# BeagleBoneCape.net
KiCad netlist of a schematic drawn in Altium Designer
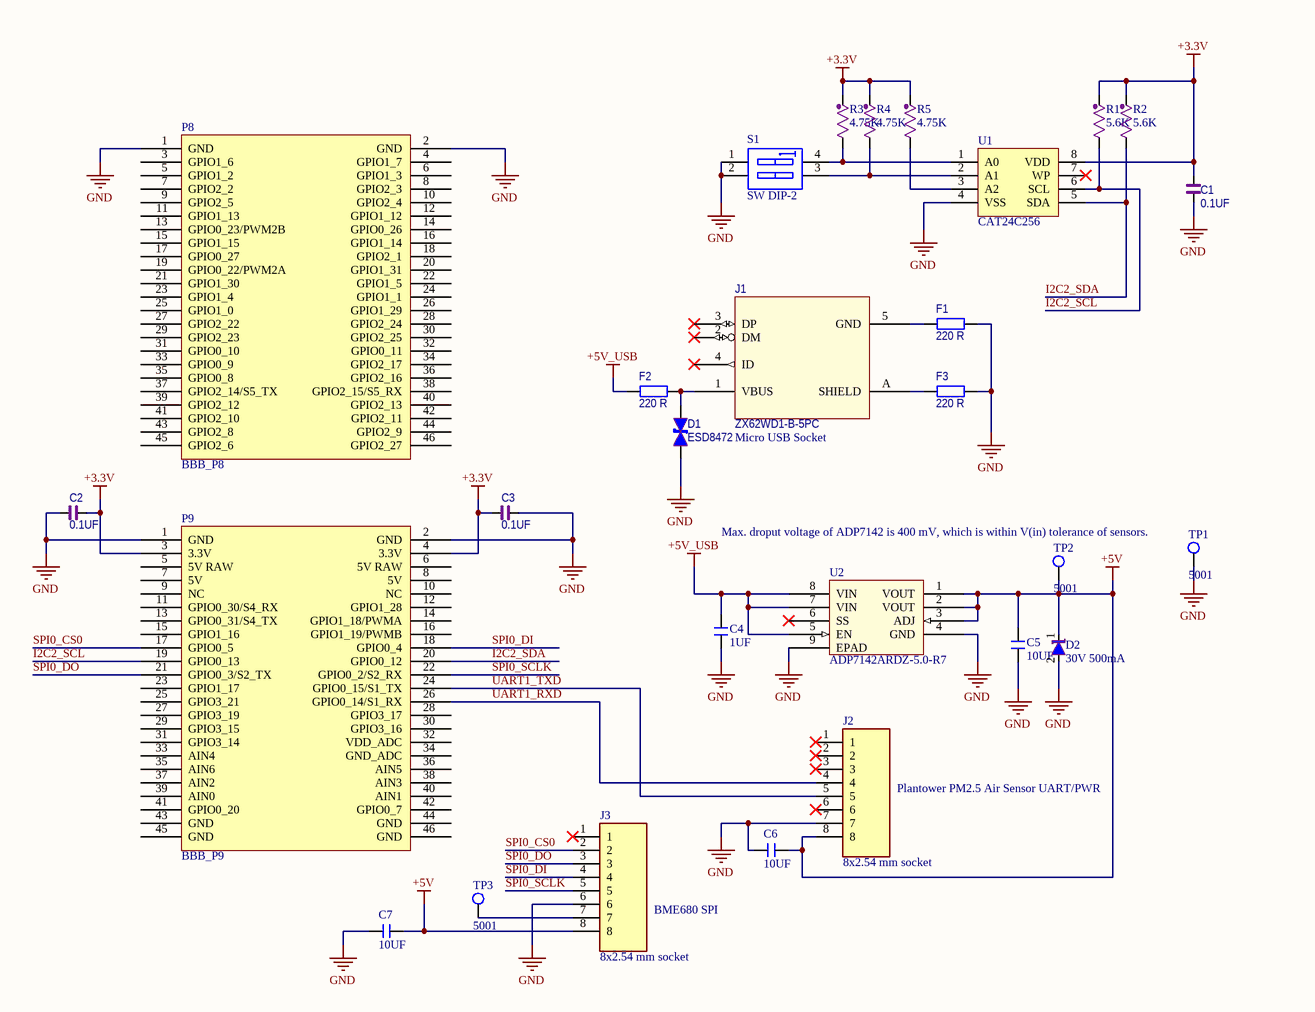
[diagram p0: BeagleBoneCape.SchDoc]

(export (version "E")
  (design (tool "Eeschema 10.0.6"))
  (components
    (comp (ref "C1")
      (value "0.1UF")
      (footprint "0603-CAP")
      (description "0.1µF ±5% 50V Ceramic Capacitor X7R 0603 (1608 Metric)")
      (fields (field (name "VOLTAGE") "50V") (field (name "TOLERANCE") "5%"))
      (libsource (lib "") (part "CAP CER 0.1UF 50V X7R 0603_1"))
    )
    (comp (ref "C2")
      (value "0.1UF")
      (footprint "0603-CAP")
      (description "0.1µF ±5% 50V Ceramic Capacitor X7R 0603 (1608 Metric)")
      (fields (field (name "VOLTAGE") "50V") (field (name "TOLERANCE") "5%"))
      (libsource (lib "BeagleBoneCape_1") (part "CAP CER 0.1UF 50V X7R 0603"))
    )
    (comp (ref "C3")
      (value "0.1UF")
      (footprint "0603-CAP")
      (description "0.1µF ±5% 50V Ceramic Capacitor X7R 0603 (1608 Metric)")
      (fields (field (name "VOLTAGE") "50V") (field (name "TOLERANCE") "5%"))
      (libsource (lib "BeagleBoneCape_1") (part "CAP CER 0.1UF 50V X7R 0603"))
    )
    (comp (ref "C4")
      (value "1UF")
      (footprint "CAPC2013X140N")
      (description "1µF ±10% 25V Ceramic Capacitor X5R 0805 (2012 Metric)")
      (fields (field (name "VOLTAGE") "25V") (field (name "TOLERANCE") "10%"))
      (libsource (lib "BeagleBoneCape_1") (part "CAP_08053D105KAT2A"))
    )
    (comp (ref "C5")
      (value "10UF")
      (footprint "CAPC2013X145N")
      (description "10µF ±10% 25V Ceramic Capacitor X5R 0805 (2012 Metric)")
      (fields (field (name "VOLTAGE") "25V") (field (name "TOLERANCE") "10%"))
      (libsource (lib "BeagleBoneCape_1") (part "CAP_C2012X5R1E106K125AB"))
    )
    (comp (ref "C6")
      (value "10UF")
      (footprint "CAPC2013X145N")
      (description "10µF ±10% 25V Ceramic Capacitor X5R 0805 (2012 Metric)")
      (fields (field (name "VOLTAGE") "25V") (field (name "TOLERANCE") "10%"))
      (libsource (lib "BeagleBoneCape_1") (part "CAP_C2012X5R1E106K125AB"))
    )
    (comp (ref "C7")
      (value "10UF")
      (footprint "CAPC2013X145N")
      (description "10µF ±10% 25V Ceramic Capacitor X5R 0805 (2012 Metric)")
      (fields (field (name "VOLTAGE") "25V") (field (name "TOLERANCE") "10%"))
      (libsource (lib "BeagleBoneCape_1") (part "CAP_C2012X5R1E106K125AB"))
    )
    (comp (ref "D1")
      (value "ESD8472")
      (footprint "0201-TVS")
      (description "20V Clamp 3A (8/20µs) Ipp Tvs Diode Surface Mount 2-X3DFN (0.62x0.32)")
      (fields (field (name "MANF") "ON SEMICONDUCTOR"))
      (libsource (lib "BeagleBoneCape_1") (part "ESD8472"))
    )
    (comp (ref "D2")
      (value "30V 500mA")
      (footprint "SOD-323")
      (description "Diode Schottky 30V 500mA (DC) Surface Mount SOD-323")
      (fields (field (name "MANF") "ON Semi"))
      (libsource (lib "BeagleBoneCape_1") (part "DIODE SCHOTTKY 30V 500MA SOD323"))
    )
    (comp (ref "F1")
      (value "220 R")
      (footprint "INDC1005X55N")
      (description "220 Ohms @ 100MHz 1  Ferrite Bead 0402 (1005 Metric) 700mA 280mOhm")
      (fields (field (name "MANF") "Murata"))
      (libsource (lib "BeagleBoneCape_1") (part "FB_BLM15EG221SN1D"))
    )
    (comp (ref "F2")
      (value "220 R")
      (footprint "INDC1005X55N")
      (description "220 Ohms @ 100MHz 1  Ferrite Bead 0402 (1005 Metric) 700mA 280mOhm")
      (fields (field (name "MANF") "Murata"))
      (libsource (lib "BeagleBoneCape_1") (part "FB_BLM15EG221SN1D"))
    )
    (comp (ref "F3")
      (value "220 R")
      (footprint "INDC1005X55N")
      (description "220 Ohms @ 100MHz 1  Ferrite Bead 0402 (1005 Metric) 700mA 280mOhm")
      (fields (field (name "MANF") "Murata"))
      (libsource (lib "BeagleBoneCape_1") (part "FB_BLM15EG221SN1D"))
    )
    (comp (ref "J1")
      (value "ZX62WD1-B-5PC")
      (footprint "HIROSE_ZX62WD1-B-5PC")
      (description "USB - micro B USB 2.0 Receptacle Connector 5 Position Surface Mount, Right Angle")
      (fields (field (name "MANF") "Hirose Electric Co Ltd") (field (name "NOTE") "Micro USB Socket"))
      (libsource (lib "BeagleBoneCape_1") (part "USB2_MICRO"))
    )
    (comp (ref "J2")
      (value "8x2.54 mm socket")
      (footprint "HDR1X8")
      (description "0.1\" 8 pin thru hole receptacle")
      (fields (field (name "MFG") "Sullins Connector Solutions"))
      (libsource (lib "BeagleBoneCape_1") (part "HDR_TH_2.54_8"))
    )
    (comp (ref "J3")
      (value "8x2.54 mm socket")
      (footprint "HDR1X8")
      (description "0.1\" 8 pin thru hole receptacle")
      (fields (field (name "MFG") "Sullins Connector Solutions"))
      (libsource (lib "BeagleBoneCape_1") (part "HDR_TH_2.54_8"))
    )
    (comp (ref "P8")
      (value "BBB_P8")
      (footprint "BBB_CAPE_HEADER")
      (libsource (lib "BeagleBoneCape_1") (part "BBB_P8"))
    )
    (comp (ref "P9")
      (value "BBB_P9")
      (footprint "BBB_CAPE_HEADER")
      (libsource (lib "BeagleBoneCape_1") (part "BBB_P9"))
    )
    (comp (ref "R1")
      (value "5.6K")
      (footprint "0603-RES")
      (description "RES SMD 5.6K 0.1% 1/10W 0603")
      (fields (field (name "MFG") "Yageo"))
      (libsource (lib "BeagleBoneCape_1") (part "RES_5.6K_0.1%_1/10_0603"))
    )
    (comp (ref "R2")
      (value "5.6K")
      (footprint "0603-RES")
      (description "RES SMD 5.6K 0.1% 1/10W 0603")
      (fields (field (name "MFG") "Yageo"))
      (libsource (lib "BeagleBoneCape_1") (part "RES_5.6K_0.1%_1/10_0603"))
    )
    (comp (ref "R3")
      (value "4.75K")
      (footprint "0603-RES")
      (description "RES SMD 4.75K 0.1% 1/10W 0603")
      (fields (field (name "MFG") "Yageo"))
      (libsource (lib "BeagleBoneCape") (part "RES_4.75K_0.1%_1/10_0603"))
    )
    (comp (ref "R4")
      (value "4.75K")
      (footprint "0603-RES")
      (description "RES SMD 4.75K 0.1% 1/10W 0603")
      (fields (field (name "MFG") "Yageo"))
      (libsource (lib "BeagleBoneCape") (part "RES_4.75K_0.1%_1/10_0603"))
    )
    (comp (ref "R5")
      (value "4.75K")
      (footprint "0603-RES")
      (description "RES SMD 4.75K 0.1% 1/10W 0603")
      (fields (field (name "MFG") "Yageo"))
      (libsource (lib "BeagleBoneCape") (part "RES_4.75K_0.1%_1/10_0603"))
    )
    (comp (ref "S1")
      (value "SW DIP-2")
      (footprint "DIP-4")
      (description "DIP Switch, 2 Position, SPST")
      (fields (field (name "PUBLISHER") "Altium Limited"))
      (libsource (lib "BeagleBoneCape_1") (part "SW DIP-2"))
    )
    (comp (ref "TP1")
      (value "5001")
      (footprint "KEYSTONE_5001")
      (description "Test Point, Black, 1-Pin THD, RoHS, Bulk")
      (fields (field (name "MANF") "Keystone"))
      (libsource (lib "BeagleBoneCape_1") (part "TP_5001"))
    )
    (comp (ref "TP2")
      (value "5001")
      (footprint "KEYSTONE_5001")
      (description "Test Point, Black, 1-Pin THD, RoHS, Bulk")
      (fields (field (name "MANF") "Keystone"))
      (libsource (lib "BeagleBoneCape_1") (part "TP_5001"))
    )
    (comp (ref "TP3")
      (value "5001")
      (footprint "KEYSTONE_5001")
      (description "Test Point, Black, 1-Pin THD, RoHS, Bulk")
      (fields (field (name "MANF") "Keystone"))
      (libsource (lib "BeagleBoneCape_1") (part "TP_5001"))
    )
    (comp (ref "U1")
      (value "CAT24C256")
      (footprint "SOIC127P600X175-8N")
      (description "EEPROM Memory IC 256Kb _32K x 8_ I2C 1MHz 500ns 8-SOIC")
      (fields (field (name "MFG") "OnSemi"))
      (libsource (lib "BeagleBoneCape_1") (part "CAT24C256"))
    )
    (comp (ref "U2")
      (value "ADP7142ARDZ-5.0-R7")
      (footprint "SOIC127P600X175-9N_ALT")
      (description "Linear Voltage Regulator IC  1 Output  200mA 8-SOIC-EP")
      (fields (field (name "MANF") "Analog Devices"))
      (libsource (lib "BeagleBoneCape_1") (part "IC_ADP7142ARDZ-5.0-R7"))
    )
  )
  (nets
    (net (code "1") (name "+3.3V") (class "Default")
      (node (ref "C1") (pin "1") (pinfunction "1_1") (pintype "passive"))
      (node (ref "C2") (pin "2") (pinfunction "2_2") (pintype "passive"))
      (node (ref "C3") (pin "1") (pinfunction "1_1") (pintype "passive"))
      (node (ref "P9") (pin "3") (pinfunction "3.3V_3") (pintype "passive"))
      (node (ref "P9") (pin "4") (pinfunction "3.3V_4") (pintype "passive"))
      (node (ref "R1") (pin "2") (pinfunction "2_2") (pintype "passive"))
      (node (ref "R2") (pin "2") (pinfunction "2_2") (pintype "passive"))
      (node (ref "R3") (pin "2") (pinfunction "2_2") (pintype "passive"))
      (node (ref "R4") (pin "2") (pinfunction "2_2") (pintype "passive"))
      (node (ref "R5") (pin "2") (pinfunction "2_2") (pintype "passive"))
      (node (ref "U1") (pin "8") (pinfunction "VDD_8") (pintype "passive"))
    )
    (net (code "2") (name "+5V") (class "Default")
      (node (ref "C5") (pin "1") (pinfunction "1_1") (pintype "passive"))
      (node (ref "C6") (pin "2") (pinfunction "2_2") (pintype "passive"))
      (node (ref "C7") (pin "1") (pinfunction "1_1") (pintype "passive"))
      (node (ref "D2") (pin "1") (pinfunction "1_1") (pintype "passive"))
      (node (ref "J2") (pin "8") (pinfunction "8_8") (pintype "passive"))
      (node (ref "J3") (pin "8") (pinfunction "8_8") (pintype "passive"))
      (node (ref "TP2") (pin "1") (pinfunction "1_1") (pintype "passive"))
      (node (ref "U2") (pin "1") (pinfunction "VOUT_1") (pintype "power_in"))
      (node (ref "U2") (pin "2") (pinfunction "VOUT_2") (pintype "power_in"))
      (node (ref "U2") (pin "3") (pinfunction "ADJ_3") (pintype "input"))
    )
    (net (code "3") (name "+5V_USB") (class "Default")
      (node (ref "C4") (pin "1") (pinfunction "1_1") (pintype "passive"))
      (node (ref "F2") (pin "1") (pinfunction "1_1") (pintype "passive"))
      (node (ref "U2") (pin "5") (pinfunction "EN_5") (pintype "input"))
      (node (ref "U2") (pin "7") (pinfunction "VIN_7") (pintype "power_in"))
      (node (ref "U2") (pin "8") (pinfunction "VIN_8") (pintype "power_in"))
    )
    (net (code "4") (name "/I2C2_SCL") (class "Default")
      (node (ref "P9") (pin "19") (pinfunction "GPIO0_13_19") (pintype "passive"))
      (node (ref "R1") (pin "1") (pinfunction "1_1") (pintype "passive"))
      (node (ref "U1") (pin "6") (pinfunction "SCL_6") (pintype "passive"))
    )
    (net (code "5") (name "/I2C2_SDA") (class "Default")
      (node (ref "P9") (pin "20") (pinfunction "GPIO0_12_20") (pintype "passive"))
      (node (ref "R2") (pin "1") (pinfunction "1_1") (pintype "passive"))
      (node (ref "U1") (pin "5") (pinfunction "SDA_5") (pintype "passive"))
    )
    (net (code "6") (name "/SPI0_CS0") (class "Default")
      (node (ref "J3") (pin "2") (pinfunction "2_2") (pintype "passive"))
      (node (ref "P9") (pin "17") (pinfunction "GPIO0_5_17") (pintype "passive"))
    )
    (net (code "7") (name "/SPI0_DI") (class "Default")
      (node (ref "J3") (pin "4") (pinfunction "4_4") (pintype "passive"))
      (node (ref "P9") (pin "18") (pinfunction "GPIO0_4_18") (pintype "passive"))
    )
    (net (code "8") (name "/SPI0_DO") (class "Default")
      (node (ref "J3") (pin "3") (pinfunction "3_3") (pintype "passive"))
      (node (ref "P9") (pin "21") (pinfunction "GPIO0_3/S2_TX_21") (pintype "passive"))
    )
    (net (code "9") (name "/SPI0_SCLK") (class "Default")
      (node (ref "J3") (pin "5") (pinfunction "5_5") (pintype "passive"))
      (node (ref "P9") (pin "22") (pinfunction "GPIO0_2/S2_RX_22") (pintype "passive"))
    )
    (net (code "10") (name "/UART1_RXD") (class "Default")
      (node (ref "J2") (pin "4") (pinfunction "4_4") (pintype "passive"))
      (node (ref "P9") (pin "26") (pinfunction "GPIO0_14/S1_RX_26") (pintype "passive"))
    )
    (net (code "11") (name "/UART1_TXD") (class "Default")
      (node (ref "J2") (pin "5") (pinfunction "5_5") (pintype "passive"))
      (node (ref "P9") (pin "24") (pinfunction "GPIO0_15/S1_TX_24") (pintype "passive"))
    )
    (net (code "12") (name "GND") (class "Default")
      (node (ref "C1") (pin "2") (pinfunction "2_2") (pintype "passive"))
      (node (ref "C2") (pin "1") (pinfunction "1_1") (pintype "passive"))
      (node (ref "C3") (pin "2") (pinfunction "2_2") (pintype "passive"))
      (node (ref "C4") (pin "2") (pinfunction "2_2") (pintype "passive"))
      (node (ref "C5") (pin "2") (pinfunction "2_2") (pintype "passive"))
      (node (ref "C6") (pin "1") (pinfunction "1_1") (pintype "passive"))
      (node (ref "C7") (pin "2") (pinfunction "2_2") (pintype "passive"))
      (node (ref "D1") (pin "1") (pinfunction "1_1") (pintype "passive"))
      (node (ref "D2") (pin "2") (pinfunction "2_2") (pintype "passive"))
      (node (ref "F1") (pin "2") (pinfunction "2_2") (pintype "passive"))
      (node (ref "F3") (pin "2") (pinfunction "2_2") (pintype "passive"))
      (node (ref "J2") (pin "7") (pinfunction "7_7") (pintype "passive"))
      (node (ref "J3") (pin "6") (pinfunction "6_6") (pintype "passive"))
      (node (ref "P8") (pin "1") (pinfunction "GND_1") (pintype "passive"))
      (node (ref "P8") (pin "2") (pinfunction "GND_2") (pintype "passive"))
      (node (ref "P9") (pin "1") (pinfunction "GND_1") (pintype "passive"))
      (node (ref "P9") (pin "2") (pinfunction "GND_2") (pintype "passive"))
      (node (ref "S1") (pin "1") (pinfunction "A1_1") (pintype "passive"))
      (node (ref "S1") (pin "2") (pinfunction "A2_2") (pintype "passive"))
      (node (ref "TP1") (pin "1") (pinfunction "1_1") (pintype "passive"))
      (node (ref "U1") (pin "4") (pinfunction "VSS_4") (pintype "passive"))
      (node (ref "U2") (pin "4") (pinfunction "GND_4") (pintype "passive"))
      (node (ref "U2") (pin "9") (pinfunction "EPAD_9") (pintype "passive"))
    )
    (net (code "13") (name "Net-(J1-GND)") (class "Default")
      (node (ref "F1") (pin "1") (pinfunction "1_1") (pintype "passive"))
      (node (ref "J1") (pin "5") (pinfunction "GND_5") (pintype "passive"))
    )
    (net (code "14") (name "Net-(J1-SHIELD)") (class "Default")
      (node (ref "F3") (pin "1") (pinfunction "1_1") (pintype "passive"))
      (node (ref "J1") (pin "A") (pinfunction "SHIELD_A") (pintype "passive"))
    )
    (net (code "15") (name "Net-(J1-VBUS)") (class "Default")
      (node (ref "D1") (pin "2") (pinfunction "2_2") (pintype "passive"))
      (node (ref "F2") (pin "2") (pinfunction "2_2") (pintype "passive"))
      (node (ref "J1") (pin "1") (pinfunction "VBUS_1") (pintype "passive"))
    )
    (net (code "16") (name "Net-(J3-Pad7)") (class "Default")
      (node (ref "J3") (pin "7") (pinfunction "7_7") (pintype "passive"))
      (node (ref "TP3") (pin "1") (pinfunction "1_1") (pintype "passive"))
    )
    (net (code "17") (name "Net-(S1-B1)") (class "Default")
      (node (ref "R3") (pin "1") (pinfunction "1_1") (pintype "passive"))
      (node (ref "S1") (pin "4") (pinfunction "B1_4") (pintype "passive"))
      (node (ref "U1") (pin "1") (pinfunction "A0_1") (pintype "passive"))
    )
    (net (code "18") (name "Net-(S1-B2)") (class "Default")
      (node (ref "R4") (pin "1") (pinfunction "1_1") (pintype "passive"))
      (node (ref "S1") (pin "3") (pinfunction "B2_3") (pintype "passive"))
      (node (ref "U1") (pin "2") (pinfunction "A1_2") (pintype "passive"))
    )
    (net (code "19") (name "Net-(U1-A2)") (class "Default")
      (node (ref "R5") (pin "1") (pinfunction "1_1") (pintype "passive"))
      (node (ref "U1") (pin "3") (pinfunction "A2_3") (pintype "passive"))
    )
    (net (code "20") (name "unconnected-(J1-DM-Pad2)") (class "Default")
      (node (ref "J1") (pin "2") (pinfunction "DM_2") (pintype "bidirectional+no_connect"))
    )
    (net (code "21") (name "unconnected-(J1-DP-Pad3)") (class "Default")
      (node (ref "J1") (pin "3") (pinfunction "DP_3") (pintype "bidirectional+no_connect"))
    )
    (net (code "22") (name "unconnected-(J1-ID-Pad4)") (class "Default")
      (node (ref "J1") (pin "4") (pinfunction "ID_4") (pintype "output+no_connect"))
    )
    (net (code "23") (name "unconnected-(J2-Pad1)") (class "Default")
      (node (ref "J2") (pin "1") (pinfunction "1_1") (pintype "passive+no_connect"))
    )
    (net (code "24") (name "unconnected-(J2-Pad2)") (class "Default")
      (node (ref "J2") (pin "2") (pinfunction "2_2") (pintype "passive+no_connect"))
    )
    (net (code "25") (name "unconnected-(J2-Pad3)") (class "Default")
      (node (ref "J2") (pin "3") (pinfunction "3_3") (pintype "passive+no_connect"))
    )
    (net (code "26") (name "unconnected-(J2-Pad6)") (class "Default")
      (node (ref "J2") (pin "6") (pinfunction "6_6") (pintype "passive+no_connect"))
    )
    (net (code "27") (name "unconnected-(J3-Pad1)") (class "Default")
      (node (ref "J3") (pin "1") (pinfunction "1_1") (pintype "passive+no_connect"))
    )
    (net (code "28") (name "unconnected-(P8-GPIO0_8-Pad35)") (class "Default")
      (node (ref "P8") (pin "35") (pinfunction "GPIO0_8_35") (pintype "passive"))
    )
    (net (code "29") (name "unconnected-(P8-GPIO0_9-Pad33)") (class "Default")
      (node (ref "P8") (pin "33") (pinfunction "GPIO0_9_33") (pintype "passive"))
    )
    (net (code "30") (name "unconnected-(P8-GPIO0_10-Pad31)") (class "Default")
      (node (ref "P8") (pin "31") (pinfunction "GPIO0_10_31") (pintype "passive"))
    )
    (net (code "31") (name "unconnected-(P8-GPIO0_11-Pad32)") (class "Default")
      (node (ref "P8") (pin "32") (pinfunction "GPIO0_11_32") (pintype "passive"))
    )
    (net (code "32") (name "unconnected-(P8-GPIO0_22{slash}PWM2A-Pad19)") (class "Default")
      (node (ref "P8") (pin "19") (pinfunction "GPIO0_22/PWM2A_19") (pintype "passive"))
    )
    (net (code "33") (name "unconnected-(P8-GPIO0_23{slash}PWM2B-Pad13)") (class "Default")
      (node (ref "P8") (pin "13") (pinfunction "GPIO0_23/PWM2B_13") (pintype "passive"))
    )
    (net (code "34") (name "unconnected-(P8-GPIO0_26-Pad14)") (class "Default")
      (node (ref "P8") (pin "14") (pinfunction "GPIO0_26_14") (pintype "passive"))
    )
    (net (code "35") (name "unconnected-(P8-GPIO0_27-Pad17)") (class "Default")
      (node (ref "P8") (pin "17") (pinfunction "GPIO0_27_17") (pintype "passive"))
    )
    (net (code "36") (name "unconnected-(P8-GPIO1_0-Pad25)") (class "Default")
      (node (ref "P8") (pin "25") (pinfunction "GPIO1_0_25") (pintype "passive"))
    )
    (net (code "37") (name "unconnected-(P8-GPIO1_1-Pad24)") (class "Default")
      (node (ref "P8") (pin "24") (pinfunction "GPIO1_1_24") (pintype "passive"))
    )
    (net (code "38") (name "unconnected-(P8-GPIO1_2-Pad5)") (class "Default")
      (node (ref "P8") (pin "5") (pinfunction "GPIO1_2_5") (pintype "passive"))
    )
    (net (code "39") (name "unconnected-(P8-GPIO1_3-Pad6)") (class "Default")
      (node (ref "P8") (pin "6") (pinfunction "GPIO1_3_6") (pintype "passive"))
    )
    (net (code "40") (name "unconnected-(P8-GPIO1_4-Pad23)") (class "Default")
      (node (ref "P8") (pin "23") (pinfunction "GPIO1_4_23") (pintype "passive"))
    )
    (net (code "41") (name "unconnected-(P8-GPIO1_5-Pad22)") (class "Default")
      (node (ref "P8") (pin "22") (pinfunction "GPIO1_5_22") (pintype "passive"))
    )
    (net (code "42") (name "unconnected-(P8-GPIO1_6-Pad3)") (class "Default")
      (node (ref "P8") (pin "3") (pinfunction "GPIO1_6_3") (pintype "passive"))
    )
    (net (code "43") (name "unconnected-(P8-GPIO1_7-Pad4)") (class "Default")
      (node (ref "P8") (pin "4") (pinfunction "GPIO1_7_4") (pintype "passive"))
    )
    (net (code "44") (name "unconnected-(P8-GPIO1_12-Pad12)") (class "Default")
      (node (ref "P8") (pin "12") (pinfunction "GPIO1_12_12") (pintype "passive"))
    )
    (net (code "45") (name "unconnected-(P8-GPIO1_13-Pad11)") (class "Default")
      (node (ref "P8") (pin "11") (pinfunction "GPIO1_13_11") (pintype "passive"))
    )
    (net (code "46") (name "unconnected-(P8-GPIO1_14-Pad16)") (class "Default")
      (node (ref "P8") (pin "16") (pinfunction "GPIO1_14_16") (pintype "passive"))
    )
    (net (code "47") (name "unconnected-(P8-GPIO1_15-Pad15)") (class "Default")
      (node (ref "P8") (pin "15") (pinfunction "GPIO1_15_15") (pintype "passive"))
    )
    (net (code "48") (name "unconnected-(P8-GPIO1_29-Pad26)") (class "Default")
      (node (ref "P8") (pin "26") (pinfunction "GPIO1_29_26") (pintype "passive"))
    )
    (net (code "49") (name "unconnected-(P8-GPIO1_30-Pad21)") (class "Default")
      (node (ref "P8") (pin "21") (pinfunction "GPIO1_30_21") (pintype "passive"))
    )
    (net (code "50") (name "unconnected-(P8-GPIO1_31-Pad20)") (class "Default")
      (node (ref "P8") (pin "20") (pinfunction "GPIO1_31_20") (pintype "passive"))
    )
    (net (code "51") (name "unconnected-(P8-GPIO2_1-Pad18)") (class "Default")
      (node (ref "P8") (pin "18") (pinfunction "GPIO2_1_18") (pintype "passive"))
    )
    (net (code "52") (name "unconnected-(P8-GPIO2_2-Pad7)") (class "Default")
      (node (ref "P8") (pin "7") (pinfunction "GPIO2_2_7") (pintype "passive"))
    )
    (net (code "53") (name "unconnected-(P8-GPIO2_3-Pad8)") (class "Default")
      (node (ref "P8") (pin "8") (pinfunction "GPIO2_3_8") (pintype "passive"))
    )
    (net (code "54") (name "unconnected-(P8-GPIO2_4-Pad10)") (class "Default")
      (node (ref "P8") (pin "10") (pinfunction "GPIO2_4_10") (pintype "passive"))
    )
    (net (code "55") (name "unconnected-(P8-GPIO2_5-Pad9)") (class "Default")
      (node (ref "P8") (pin "9") (pinfunction "GPIO2_5_9") (pintype "passive"))
    )
    (net (code "56") (name "unconnected-(P8-GPIO2_6-Pad45)") (class "Default")
      (node (ref "P8") (pin "45") (pinfunction "GPIO2_6_45") (pintype "passive"))
    )
    (net (code "57") (name "unconnected-(P8-GPIO2_8-Pad43)") (class "Default")
      (node (ref "P8") (pin "43") (pinfunction "GPIO2_8_43") (pintype "passive"))
    )
    (net (code "58") (name "unconnected-(P8-GPIO2_9-Pad44)") (class "Default")
      (node (ref "P8") (pin "44") (pinfunction "GPIO2_9_44") (pintype "passive"))
    )
    (net (code "59") (name "unconnected-(P8-GPIO2_10-Pad41)") (class "Default")
      (node (ref "P8") (pin "41") (pinfunction "GPIO2_10_41") (pintype "passive"))
    )
    (net (code "60") (name "unconnected-(P8-GPIO2_11-Pad42)") (class "Default")
      (node (ref "P8") (pin "42") (pinfunction "GPIO2_11_42") (pintype "passive"))
    )
    (net (code "61") (name "unconnected-(P8-GPIO2_12-Pad39)") (class "Default")
      (node (ref "P8") (pin "39") (pinfunction "GPIO2_12_39") (pintype "passive"))
    )
    (net (code "62") (name "unconnected-(P8-GPIO2_13-Pad40)") (class "Default")
      (node (ref "P8") (pin "40") (pinfunction "GPIO2_13_40") (pintype "passive"))
    )
    (net (code "63") (name "unconnected-(P8-GPIO2_14{slash}S5_TX-Pad37)") (class "Default")
      (node (ref "P8") (pin "37") (pinfunction "GPIO2_14/S5_TX_37") (pintype "passive"))
    )
    (net (code "64") (name "unconnected-(P8-GPIO2_15{slash}S5_RX-Pad38)") (class "Default")
      (node (ref "P8") (pin "38") (pinfunction "GPIO2_15/S5_RX_38") (pintype "passive"))
    )
    (net (code "65") (name "unconnected-(P8-GPIO2_16-Pad36)") (class "Default")
      (node (ref "P8") (pin "36") (pinfunction "GPIO2_16_36") (pintype "passive"))
    )
    (net (code "66") (name "unconnected-(P8-GPIO2_17-Pad34)") (class "Default")
      (node (ref "P8") (pin "34") (pinfunction "GPIO2_17_34") (pintype "passive"))
    )
    (net (code "67") (name "unconnected-(P8-GPIO2_22-Pad27)") (class "Default")
      (node (ref "P8") (pin "27") (pinfunction "GPIO2_22_27") (pintype "passive"))
    )
    (net (code "68") (name "unconnected-(P8-GPIO2_23-Pad29)") (class "Default")
      (node (ref "P8") (pin "29") (pinfunction "GPIO2_23_29") (pintype "passive"))
    )
    (net (code "69") (name "unconnected-(P8-GPIO2_24-Pad28)") (class "Default")
      (node (ref "P8") (pin "28") (pinfunction "GPIO2_24_28") (pintype "passive"))
    )
    (net (code "70") (name "unconnected-(P8-GPIO2_25-Pad30)") (class "Default")
      (node (ref "P8") (pin "30") (pinfunction "GPIO2_25_30") (pintype "passive"))
    )
    (net (code "71") (name "unconnected-(P8-GPIO2_27-Pad46)") (class "Default")
      (node (ref "P8") (pin "46") (pinfunction "GPIO2_27_46") (pintype "passive"))
    )
    (net (code "72") (name "unconnected-(P9-5V-Pad7)") (class "Default")
      (node (ref "P9") (pin "7") (pinfunction "5V_7") (pintype "passive"))
    )
    (net (code "73") (name "unconnected-(P9-5V-Pad8)") (class "Default")
      (node (ref "P9") (pin "8") (pinfunction "5V_8") (pintype "passive"))
    )
    (net (code "74") (name "unconnected-(P9-5V_RAW-Pad5)") (class "Default")
      (node (ref "P9") (pin "5") (pinfunction "5V_RAW_5") (pintype "passive"))
    )
    (net (code "75") (name "unconnected-(P9-5V_RAW-Pad6)") (class "Default")
      (node (ref "P9") (pin "6") (pinfunction "5V_RAW_6") (pintype "passive"))
    )
    (net (code "76") (name "unconnected-(P9-AIN0-Pad39)") (class "Default")
      (node (ref "P9") (pin "39") (pinfunction "AIN0_39") (pintype "passive"))
    )
    (net (code "77") (name "unconnected-(P9-AIN1-Pad40)") (class "Default")
      (node (ref "P9") (pin "40") (pinfunction "AIN1_40") (pintype "passive"))
    )
    (net (code "78") (name "unconnected-(P9-AIN2-Pad37)") (class "Default")
      (node (ref "P9") (pin "37") (pinfunction "AIN2_37") (pintype "passive"))
    )
    (net (code "79") (name "unconnected-(P9-AIN3-Pad38)") (class "Default")
      (node (ref "P9") (pin "38") (pinfunction "AIN3_38") (pintype "passive"))
    )
    (net (code "80") (name "unconnected-(P9-AIN4-Pad33)") (class "Default")
      (node (ref "P9") (pin "33") (pinfunction "AIN4_33") (pintype "passive"))
    )
    (net (code "81") (name "unconnected-(P9-AIN5-Pad36)") (class "Default")
      (node (ref "P9") (pin "36") (pinfunction "AIN5_36") (pintype "passive"))
    )
    (net (code "82") (name "unconnected-(P9-AIN6-Pad35)") (class "Default")
      (node (ref "P9") (pin "35") (pinfunction "AIN6_35") (pintype "passive"))
    )
    (net (code "83") (name "unconnected-(P9-GND-Pad43)") (class "Default")
      (node (ref "P9") (pin "43") (pinfunction "GND_43") (pintype "passive"))
    )
    (net (code "84") (name "unconnected-(P9-GND-Pad44)") (class "Default")
      (node (ref "P9") (pin "44") (pinfunction "GND_44") (pintype "passive"))
    )
    (net (code "85") (name "unconnected-(P9-GND-Pad45)") (class "Default")
      (node (ref "P9") (pin "45") (pinfunction "GND_45") (pintype "passive"))
    )
    (net (code "86") (name "unconnected-(P9-GND-Pad46)") (class "Default")
      (node (ref "P9") (pin "46") (pinfunction "GND_46") (pintype "passive"))
    )
    (net (code "87") (name "unconnected-(P9-GND_ADC-Pad34)") (class "Default")
      (node (ref "P9") (pin "34") (pinfunction "GND_ADC_34") (pintype "passive"))
    )
    (net (code "88") (name "unconnected-(P9-GPIO0_7-Pad42)") (class "Default")
      (node (ref "P9") (pin "42") (pinfunction "GPIO0_7_42") (pintype "passive"))
    )
    (net (code "89") (name "unconnected-(P9-GPIO0_20-Pad41)") (class "Default")
      (node (ref "P9") (pin "41") (pinfunction "GPIO0_20_41") (pintype "passive"))
    )
    (net (code "90") (name "unconnected-(P9-GPIO0_30{slash}S4_RX-Pad11)") (class "Default")
      (node (ref "P9") (pin "11") (pinfunction "GPIO0_30/S4_RX_11") (pintype "passive"))
    )
    (net (code "91") (name "unconnected-(P9-GPIO0_31{slash}S4_TX-Pad13)") (class "Default")
      (node (ref "P9") (pin "13") (pinfunction "GPIO0_31/S4_TX_13") (pintype "passive"))
    )
    (net (code "92") (name "unconnected-(P9-GPIO1_16-Pad15)") (class "Default")
      (node (ref "P9") (pin "15") (pinfunction "GPIO1_16_15") (pintype "passive"))
    )
    (net (code "93") (name "unconnected-(P9-GPIO1_17-Pad23)") (class "Default")
      (node (ref "P9") (pin "23") (pinfunction "GPIO1_17_23") (pintype "passive"))
    )
    (net (code "94") (name "unconnected-(P9-GPIO1_18{slash}PWMA-Pad14)") (class "Default")
      (node (ref "P9") (pin "14") (pinfunction "GPIO1_18/PWMA_14") (pintype "passive"))
    )
    (net (code "95") (name "unconnected-(P9-GPIO1_19{slash}PWMB-Pad16)") (class "Default")
      (node (ref "P9") (pin "16") (pinfunction "GPIO1_19/PWMB_16") (pintype "passive"))
    )
    (net (code "96") (name "unconnected-(P9-GPIO1_28-Pad12)") (class "Default")
      (node (ref "P9") (pin "12") (pinfunction "GPIO1_28_12") (pintype "passive"))
    )
    (net (code "97") (name "unconnected-(P9-GPIO3_14-Pad31)") (class "Default")
      (node (ref "P9") (pin "31") (pinfunction "GPIO3_14_31") (pintype "passive"))
    )
    (net (code "98") (name "unconnected-(P9-GPIO3_15-Pad29)") (class "Default")
      (node (ref "P9") (pin "29") (pinfunction "GPIO3_15_29") (pintype "passive"))
    )
    (net (code "99") (name "unconnected-(P9-GPIO3_16-Pad30)") (class "Default")
      (node (ref "P9") (pin "30") (pinfunction "GPIO3_16_30") (pintype "passive"))
    )
    (net (code "100") (name "unconnected-(P9-GPIO3_17-Pad28)") (class "Default")
      (node (ref "P9") (pin "28") (pinfunction "GPIO3_17_28") (pintype "passive"))
    )
    (net (code "101") (name "unconnected-(P9-GPIO3_19-Pad27)") (class "Default")
      (node (ref "P9") (pin "27") (pinfunction "GPIO3_19_27") (pintype "passive"))
    )
    (net (code "102") (name "unconnected-(P9-GPIO3_21-Pad25)") (class "Default")
      (node (ref "P9") (pin "25") (pinfunction "GPIO3_21_25") (pintype "passive"))
    )
    (net (code "103") (name "unconnected-(P9-NC-Pad9)") (class "Default")
      (node (ref "P9") (pin "9") (pinfunction "NC_9") (pintype "passive"))
    )
    (net (code "104") (name "unconnected-(P9-NC-Pad10)") (class "Default")
      (node (ref "P9") (pin "10") (pinfunction "NC_10") (pintype "passive"))
    )
    (net (code "105") (name "unconnected-(P9-VDD_ADC-Pad32)") (class "Default")
      (node (ref "P9") (pin "32") (pinfunction "VDD_ADC_32") (pintype "passive"))
    )
    (net (code "106") (name "unconnected-(U1-WP-Pad7)") (class "Default")
      (node (ref "U1") (pin "7") (pinfunction "WP_7") (pintype "passive+no_connect"))
    )
    (net (code "107") (name "unconnected-(U2-SS-Pad6)") (class "Default")
      (node (ref "U2") (pin "6") (pinfunction "SS_6") (pintype "passive+no_connect"))
    )
  )
)
